# Power.net
KiCad netlist of a schematic drawn in Altium Designer
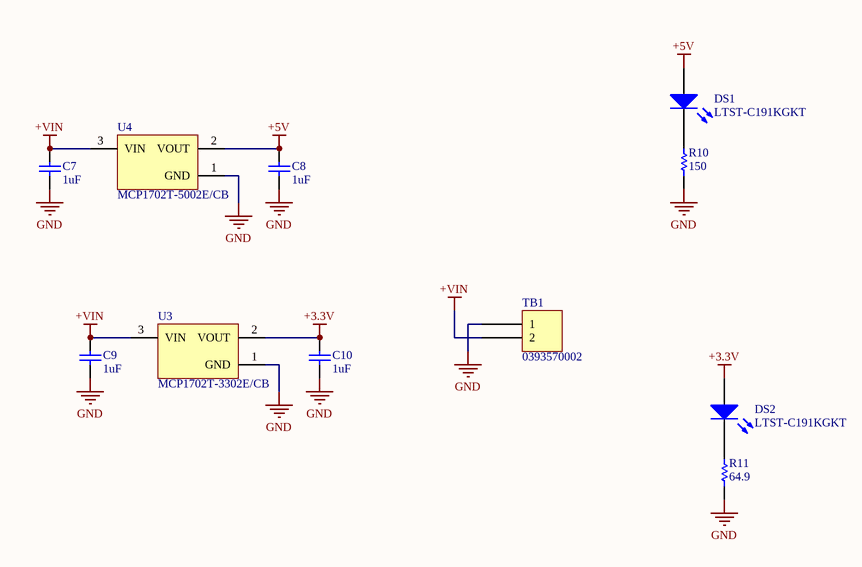
[diagram p0: Power.SchDoc]

(export (version "E")
  (design (tool "Eeschema 10.0.6"))
  (components
    (comp (ref "C7")
      (value "1uF")
      (footprint "0603")
      (fields
        (field (name "MANUFACTURER") "TDK")
        (field (name "MANUFACTURER PART NUMBER") "C1608X7R1C105K080AC")
        (field (name "VOLTAGE") "16V")
      )
      (libsource (lib "altium-library") (part "Capacitor"))
    )
    (comp (ref "C8")
      (value "1uF")
      (footprint "0603")
      (fields
        (field (name "MANUFACTURER") "TDK")
        (field (name "MANUFACTURER PART NUMBER") "C1608X7R1C105K080AC")
        (field (name "VOLTAGE") "16V")
      )
      (libsource (lib "altium-library") (part "Capacitor"))
    )
    (comp (ref "C9")
      (value "1uF")
      (footprint "0603")
      (fields
        (field (name "MANUFACTURER") "TDK")
        (field (name "MANUFACTURER PART NUMBER") "C1608X7R1C105K080AC")
        (field (name "VOLTAGE") "16V")
      )
      (libsource (lib "altium-library") (part "Capacitor"))
    )
    (comp (ref "C10")
      (value "1uF")
      (footprint "0603")
      (fields
        (field (name "MANUFACTURER") "TDK")
        (field (name "MANUFACTURER PART NUMBER") "C1608X7R1C105K080AC")
        (field (name "VOLTAGE") "16V")
      )
      (libsource (lib "altium-library") (part "Capacitor"))
    )
    (comp (ref "DS1")
      (value "LTST-C191KGKT")
      (footprint "LITE-ON-LTST-C191KRKT-2_V")
      (description "Chip LED, Green, 574 nm, 40 pF, -55 to 85 degC, 2-Pin SMD, RoHS, Tape and Reel")
      (fields (field (name "MANUFACTURER") "Lite-On"))
      (libsource (lib "Altium Content Vault") (part "LED-AK-2"))
    )
    (comp (ref "DS2")
      (value "LTST-C191KGKT")
      (footprint "LITE-ON-LTST-C191KRKT-2_V")
      (description "Chip LED, Green, 574 nm, 40 pF, -55 to 85 degC, 2-Pin SMD, RoHS, Tape and Reel")
      (fields (field (name "MANUFACTURER") "Lite-On"))
      (libsource (lib "Altium Content Vault") (part "LED-AK-2"))
    )
    (comp (ref "R10")
      (value "150")
      (footprint "0402")
      (description "Resistor;  Thick Film;  150 Ohms;  0.063 W;  1%;  SMT;  0402;  TCR 37 ppm/DegC")
      (fields
        (field (name "MANUFACTURER") "Vishay")
        (field (name "MANUFACTURER PART NUMBER") "CRCW0402150RFKED")
      )
      (libsource (lib "altium-library") (part "Resistor"))
    )
    (comp (ref "R11")
      (value "64.9")
      (footprint "0402")
      (fields
        (field (name "MANUFACTURER") "Vishay")
        (field (name "MANUFACTURER PART NUMBER") "CRCW040264R9FKED")
        (field (name "TOLERANCE") "1%")
      )
      (libsource (lib "altium-library") (part "Resistor"))
    )
    (comp (ref "TB1")
      (value "0393570002")
      (footprint "0393570002")
      (description "Conn Eurostyle Block 2 POS 3.5mm Solder ST Thru-Hole 17.5A/Contact Eurostyle™")
      (fields (field (name "MANUFACTURER") "Molex") (field (name "VOLTAGE") "300V"))
      (libsource (lib "altium-library") (part "0393570002"))
    )
    (comp (ref "U3")
      (value "MCP1702T-3302E/CB")
      (footprint "SOT-23A-CB3_N")
      (description "250 mA Low Quiescent Current LDO Regulator, 3-Pin SOT-23A, Extended Temperature, Tape and Reel")
      (libsource (lib "Altium Content Vault") (part "PM-LINEREG-MCP1702-IL3"))
    )
    (comp (ref "U4")
      (value "MCP1702T-5002E/CB")
      (footprint "SOT-23A-CB3_N")
      (description "250 mA Low Quiescent Current LDO Regulator, 3-Pin SOT-23A, Extended Temperature, Tape and Reel")
      (libsource (lib "Altium Content Vault") (part "PM-LINEREG-MCP1702-IL3"))
    )
  )
  (nets
    (net (code "1") (name "+3.3V") (class "Default")
      (node (ref "C10") (pin "2") (pinfunction "2_2") (pintype "passive"))
      (node (ref "DS2") (pin "1") (pinfunction "A_1") (pintype "passive"))
      (node (ref "U3") (pin "2") (pinfunction "VOUT_2") (pintype "power_in"))
    )
    (net (code "2") (name "+5V") (class "Default")
      (node (ref "C8") (pin "2") (pinfunction "2_2") (pintype "passive"))
      (node (ref "DS1") (pin "1") (pinfunction "A_1") (pintype "passive"))
      (node (ref "U4") (pin "2") (pinfunction "VOUT_2") (pintype "power_in"))
    )
    (net (code "3") (name "+VIN") (class "Default")
      (node (ref "C7") (pin "2") (pinfunction "2_2") (pintype "passive"))
      (node (ref "C9") (pin "2") (pinfunction "2_2") (pintype "passive"))
      (node (ref "TB1") (pin "2") (pinfunction "2_2") (pintype "passive"))
      (node (ref "U3") (pin "3") (pinfunction "VIN_3") (pintype "power_in"))
      (node (ref "U4") (pin "3") (pinfunction "VIN_3") (pintype "power_in"))
    )
    (net (code "4") (name "GND") (class "Default")
      (node (ref "C10") (pin "1") (pinfunction "1_1") (pintype "passive"))
      (node (ref "C7") (pin "1") (pinfunction "1_1") (pintype "passive"))
      (node (ref "C8") (pin "1") (pinfunction "1_1") (pintype "passive"))
      (node (ref "C9") (pin "1") (pinfunction "1_1") (pintype "passive"))
      (node (ref "R10") (pin "1") (pinfunction "1_1") (pintype "passive"))
      (node (ref "R11") (pin "1") (pinfunction "1_1") (pintype "passive"))
      (node (ref "TB1") (pin "1") (pinfunction "1_1") (pintype "passive"))
      (node (ref "U3") (pin "1") (pinfunction "GND_1") (pintype "power_in"))
      (node (ref "U4") (pin "1") (pinfunction "GND_1") (pintype "power_in"))
    )
    (net (code "5") (name "Net-(DS1-K)") (class "Default")
      (node (ref "DS1") (pin "2") (pinfunction "K_2") (pintype "passive"))
      (node (ref "R10") (pin "2") (pinfunction "2_2") (pintype "passive"))
    )
    (net (code "6") (name "Net-(DS2-K)") (class "Default")
      (node (ref "DS2") (pin "2") (pinfunction "K_2") (pintype "passive"))
      (node (ref "R11") (pin "2") (pinfunction "2_2") (pintype "passive"))
    )
  )
)
